# LSM6DSM_breakout.net
KiCad netlist of a schematic drawn in EAGLE
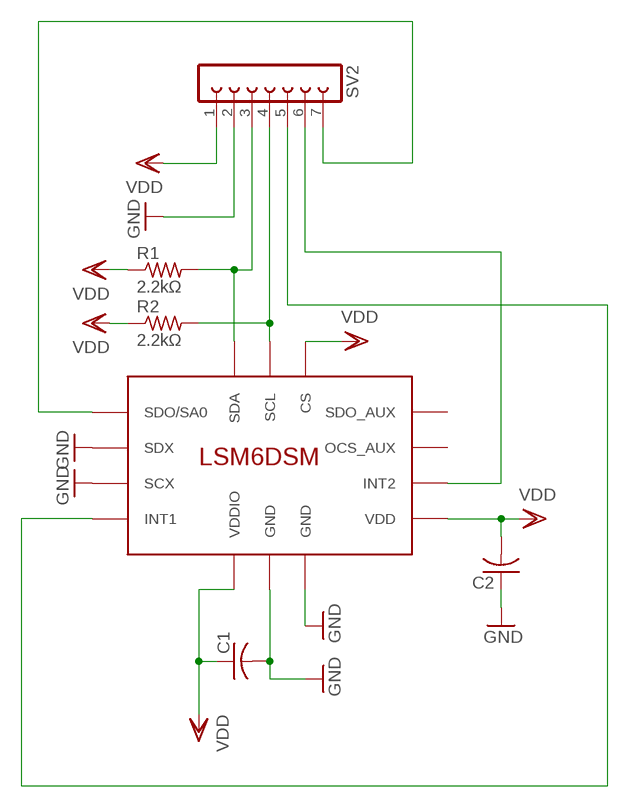
[diagram p0: schematic, sheet 1]

(export (version "E")
  (design (tool "Eeschema 10.0.6"))
  (components
    (comp (ref "C1")
      (value "C-USC0805")
      (footprint "eagle-import:C0805")
      (libsource (lib "eagle-import") (part "C-USC0805"))
    )
    (comp (ref "C2")
      (value "C-USC0805")
      (footprint "eagle-import:C0805")
      (libsource (lib "eagle-import") (part "C-USC0805"))
    )
    (comp (ref "R1")
      (value "2.2kΩ")
      (footprint "eagle-import:M0805")
      (libsource (lib "eagle-import") (part "R-US_M0805"))
    )
    (comp (ref "R2")
      (value "2.2kΩ")
      (footprint "eagle-import:M0805")
      (libsource (lib "eagle-import") (part "R-US_M0805"))
    )
    (comp (ref "SV2")
      (value "FE07-1")
      (footprint "eagle-import:FE07")
      (libsource (lib "eagle-import") (part "FE07-1"))
    )
    (comp (ref "U$1")
      (value "LSM6DSM")
      (footprint "eagle-import:LSM6DSM")
      (libsource (lib "eagle-import") (part "LSM6DSM"))
    )
  )
  (nets
    (net (code "1") (name "GND") (class "Default")
      (node (ref "C1") (pin "2") (pinfunction "2_2") (pintype "passive"))
      (node (ref "C2") (pin "1") (pinfunction "1_1") (pintype "passive"))
      (node (ref "SV2") (pin "2") (pinfunction "2_2") (pintype "passive"))
      (node (ref "U$1") (pin "GND@1") (pinfunction "GND_GND@1") (pintype "bidirectional"))
      (node (ref "U$1") (pin "GND@2") (pinfunction "GND_GND@2") (pintype "bidirectional"))
      (node (ref "U$1") (pin "SCX") (pinfunction "SCX_SCX") (pintype "bidirectional"))
      (node (ref "U$1") (pin "SDX") (pinfunction "SDX_SDX") (pintype "bidirectional"))
    )
    (net (code "2") (name "Net-(R1-Pad2)") (class "Default")
      (node (ref "R1") (pin "2") (pinfunction "2_2") (pintype "passive"))
      (node (ref "SV2") (pin "3") (pinfunction "3_3") (pintype "passive"))
      (node (ref "U$1") (pin "SDA") (pinfunction "SDA_SDA") (pintype "bidirectional"))
    )
    (net (code "3") (name "Net-(R2-Pad2)") (class "Default")
      (node (ref "R2") (pin "2") (pinfunction "2_2") (pintype "passive"))
      (node (ref "SV2") (pin "4") (pinfunction "4_4") (pintype "passive"))
      (node (ref "U$1") (pin "SCL") (pinfunction "SCL_SCL") (pintype "bidirectional"))
    )
    (net (code "4") (name "Net-(SV2-Pad5)") (class "Default")
      (node (ref "SV2") (pin "5") (pinfunction "5_5") (pintype "passive"))
      (node (ref "U$1") (pin "INT1") (pinfunction "INT1_INT1") (pintype "bidirectional"))
    )
    (net (code "5") (name "Net-(SV2-Pad6)") (class "Default")
      (node (ref "SV2") (pin "6") (pinfunction "6_6") (pintype "passive"))
      (node (ref "U$1") (pin "INT2") (pinfunction "INT2_INT2") (pintype "bidirectional"))
    )
    (net (code "6") (name "Net-(SV2-Pad7)") (class "Default")
      (node (ref "SV2") (pin "7") (pinfunction "7_7") (pintype "passive"))
      (node (ref "U$1") (pin "SDO/SA0") (pinfunction "SDO/SA0_SDO/SA0") (pintype "bidirectional"))
    )
    (net (code "7") (name "VDD") (class "Default")
      (node (ref "C1") (pin "1") (pinfunction "1_1") (pintype "passive"))
      (node (ref "C2") (pin "2") (pinfunction "2_2") (pintype "passive"))
      (node (ref "R1") (pin "1") (pinfunction "1_1") (pintype "passive"))
      (node (ref "R2") (pin "1") (pinfunction "1_1") (pintype "passive"))
      (node (ref "SV2") (pin "1") (pinfunction "1_1") (pintype "passive"))
      (node (ref "U$1") (pin "CS") (pinfunction "CS_CS") (pintype "bidirectional"))
      (node (ref "U$1") (pin "VDD") (pinfunction "VDD_VDD") (pintype "bidirectional"))
      (node (ref "U$1") (pin "VDDIO") (pinfunction "VDDIO_VDDIO") (pintype "bidirectional"))
    )
    (net (code "8") (name "unconnected-(U$1-PadOCS_AUX)") (class "Default")
      (node (ref "U$1") (pin "OCS_AUX") (pinfunction "OCS_AUX_OCS_AUX") (pintype "bidirectional"))
    )
    (net (code "9") (name "unconnected-(U$1-PadSDO_AUX)") (class "Default")
      (node (ref "U$1") (pin "SDO_AUX") (pinfunction "SDO_AUX_SDO_AUX") (pintype "bidirectional"))
    )
  )
)
